# RS485.net
KiCad netlist of a schematic drawn in Altium Designer
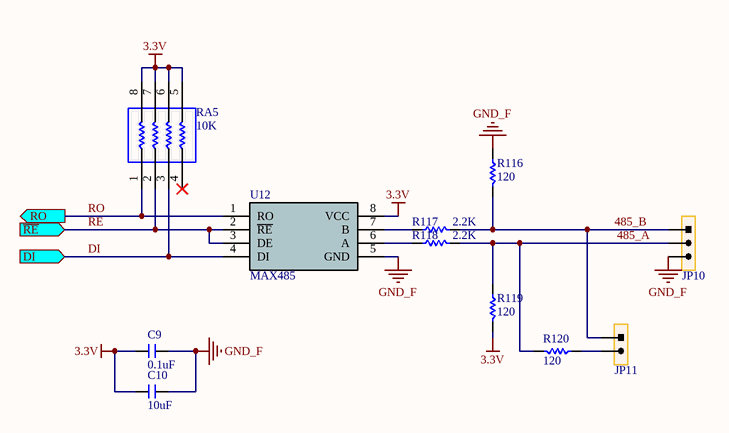
[diagram p0: RS485.SchDoc]

(export (version "E")
  (design (tool "Eeschema 10.0.6"))
  (components
    (comp (ref "C9")
      (value "0.1uF")
      (footprint "C 0805")
      (description "Non-polar patch capacitor")
      (fields (field (name "版权归属") "源创客"))
      (libsource (lib "") (part "C_1"))
    )
    (comp (ref "C10")
      (value "10uF")
      (footprint "C 0805")
      (description "Non-polar patch capacitor")
      (fields (field (name "版权归属") "源创客"))
      (libsource (lib "Passive (Resistor-Capacitor-Inductor-Veristor-Ferrite)") (part "C"))
    )
    (comp (ref "JP10")
      (value "HDR-1X3")
      (footprint "KF2EDGK-3P_H_5.08")
      (description "3P Connector")
      (fields (field (name "版权归属") "源创客"))
      (libsource (lib "Connectors") (part "Header 3"))
    )
    (comp (ref "JP11")
      (value "HDR-1X2")
      (footprint "HDR-1X2")
      (description "2P Connector")
      (fields (field (name "版权归属") "源创客"))
      (libsource (lib "Connectors") (part "Header 2"))
    )
    (comp (ref "R116")
      (value "120")
      (footprint "R 0805")
      (description "Chip resistor")
      (fields (field (name "版权归属") "源创客"))
      (libsource (lib "Passive (Resistor-Capacitor-Inductor-Veristor-Ferrite)") (part "R"))
    )
    (comp (ref "R117")
      (value "2.2K")
      (footprint "R 0805")
      (description "Chip resistor")
      (fields (field (name "版权归属") "源创客"))
      (libsource (lib "Passive (Resistor-Capacitor-Inductor-Veristor-Ferrite)") (part "R"))
    )
    (comp (ref "R118")
      (value "2.2K")
      (footprint "R 0805")
      (description "Chip resistor")
      (fields (field (name "版权归属") "源创客"))
      (libsource (lib "Passive (Resistor-Capacitor-Inductor-Veristor-Ferrite)") (part "R"))
    )
    (comp (ref "R119")
      (value "120")
      (footprint "R 0805")
      (description "Chip resistor")
      (fields (field (name "版权归属") "源创客"))
      (libsource (lib "Passive (Resistor-Capacitor-Inductor-Veristor-Ferrite)") (part "R"))
    )
    (comp (ref "R120")
      (value "120")
      (footprint "R 0805")
      (description "Chip resistor")
      (fields (field (name "版权归属") "源创客"))
      (libsource (lib "Passive (Resistor-Capacitor-Inductor-Veristor-Ferrite)") (part "R"))
    )
    (comp (ref "RA5")
      (value "10K")
      (footprint "RA1206 (4x0603)")
      (description "4 way Chip Resistor Array")
      (libsource (lib "Passive (Resistor-Capacitor-Inductor-Veristor-Ferrite)") (part "R-ARR"))
    )
    (comp (ref "U12")
      (value "MAX485")
      (footprint "SOP8_N")
      (description "RS485/RS422 Transceivers")
      (fields (field (name "版权归属") "源创客"))
      (libsource (lib "Integrated Circuit") (part "MAX485"))
    )
  )
  (nets
    (net (code "1") (name "/485_A") (class "Default")
      (node (ref "JP10") (pin "2") (pintype "passive"))
      (node (ref "R118") (pin "2") (pinfunction "2_2") (pintype "passive"))
      (node (ref "R119") (pin "1") (pinfunction "1_1") (pintype "passive"))
      (node (ref "R120") (pin "2") (pinfunction "2_2") (pintype "passive"))
    )
    (net (code "2") (name "/485_B") (class "Default")
      (node (ref "JP10") (pin "1") (pintype "passive"))
      (node (ref "JP11") (pin "1") (pintype "passive"))
      (node (ref "R116") (pin "2") (pinfunction "2_2") (pintype "passive"))
      (node (ref "R117") (pin "2") (pinfunction "2_2") (pintype "passive"))
    )
    (net (code "3") (name "/DI") (class "Default")
      (node (ref "RA5") (pin "3") (pinfunction "3_3") (pintype "passive"))
      (node (ref "U12") (pin "4") (pinfunction "DI_4") (pintype "passive"))
    )
    (net (code "4") (name "/RO") (class "Default")
      (node (ref "RA5") (pin "1") (pinfunction "1_1") (pintype "passive"))
      (node (ref "U12") (pin "1") (pinfunction "RO_1") (pintype "passive"))
    )
    (net (code "5") (name "/~{RE}") (class "Default")
      (node (ref "RA5") (pin "2") (pinfunction "2_2") (pintype "passive"))
      (node (ref "U12") (pin "2") (pinfunction "~{RE}_2") (pintype "passive"))
      (node (ref "U12") (pin "3") (pinfunction "DE_3") (pintype "passive"))
    )
    (net (code "6") (name "3.3V") (class "Default")
      (node (ref "C10") (pin "1") (pinfunction "1_1") (pintype "passive"))
      (node (ref "C9") (pin "1") (pinfunction "1_1") (pintype "passive"))
      (node (ref "R119") (pin "2") (pinfunction "2_2") (pintype "passive"))
      (node (ref "RA5") (pin "5") (pinfunction "5_5") (pintype "passive"))
      (node (ref "RA5") (pin "6") (pinfunction "6_6") (pintype "passive"))
      (node (ref "RA5") (pin "7") (pinfunction "7_7") (pintype "passive"))
      (node (ref "RA5") (pin "8") (pinfunction "8_8") (pintype "passive"))
      (node (ref "U12") (pin "8") (pinfunction "VCC_8") (pintype "passive"))
    )
    (net (code "7") (name "GND_F") (class "Default")
      (node (ref "C10") (pin "2") (pinfunction "2_2") (pintype "passive"))
      (node (ref "C9") (pin "2") (pinfunction "2_2") (pintype "passive"))
      (node (ref "JP10") (pin "3") (pintype "passive"))
      (node (ref "R116") (pin "1") (pinfunction "1_1") (pintype "passive"))
      (node (ref "U12") (pin "5") (pinfunction "GND_5") (pintype "passive"))
    )
    (net (code "8") (name "Net-(JP11-Pad2)") (class "Default")
      (node (ref "JP11") (pin "2") (pintype "passive"))
      (node (ref "R120") (pin "1") (pinfunction "1_1") (pintype "passive"))
    )
    (net (code "9") (name "Net-(U12-A)") (class "Default")
      (node (ref "R118") (pin "1") (pinfunction "1_1") (pintype "passive"))
      (node (ref "U12") (pin "6") (pinfunction "A_6") (pintype "passive"))
    )
    (net (code "10") (name "Net-(U12-B)") (class "Default")
      (node (ref "R117") (pin "1") (pinfunction "1_1") (pintype "passive"))
      (node (ref "U12") (pin "7") (pinfunction "B_7") (pintype "passive"))
    )
    (net (code "11") (name "unconnected-(RA5-Pad4)") (class "Default")
      (node (ref "RA5") (pin "4") (pinfunction "4_4") (pintype "passive+no_connect"))
    )
  )
)
